# DS18B20_Control_Industry.net
KiCad netlist of a schematic drawn in Altium Designer
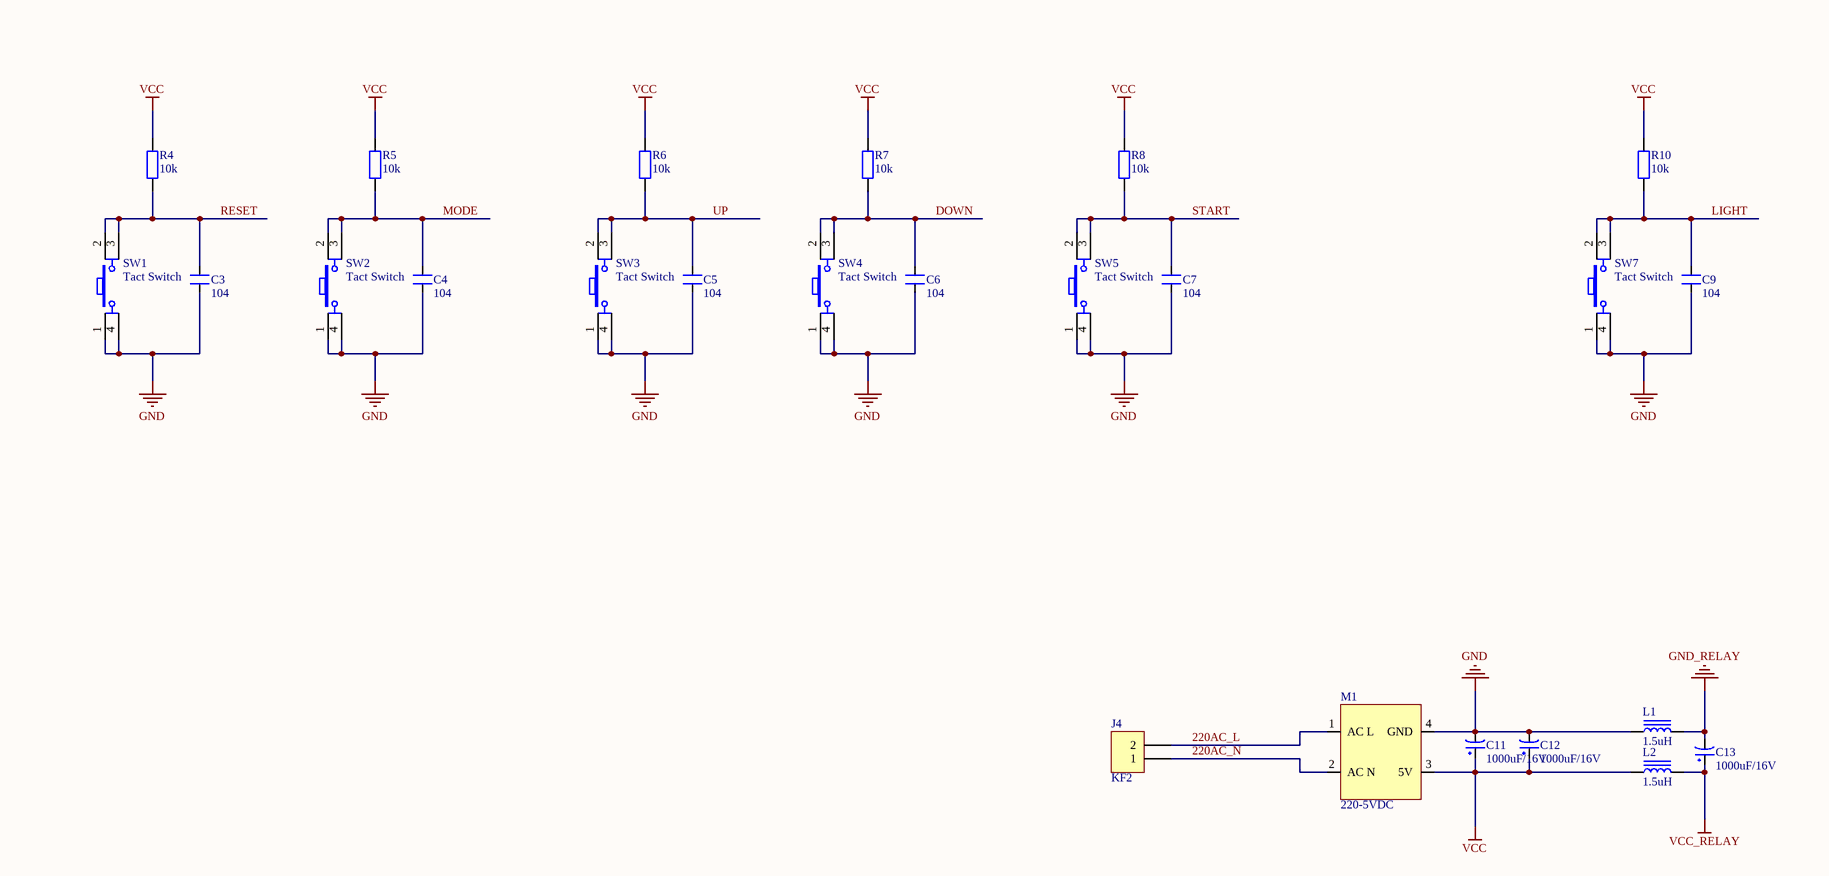
[diagram p0: DS18B20_Control_Industry.SchDoc, top left]
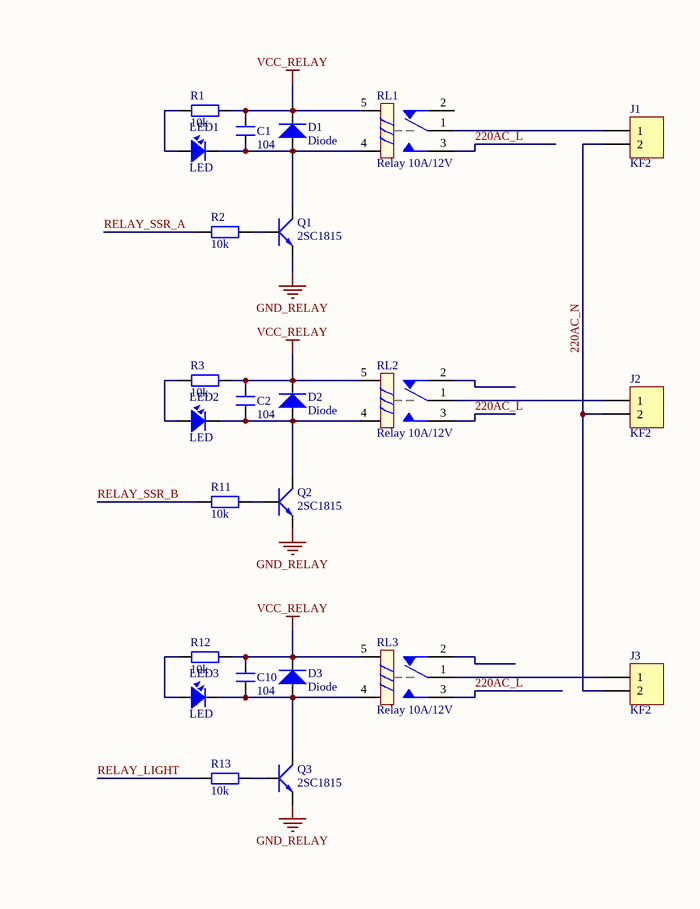
[diagram p1: DS18B20_Control_Industry.SchDoc, top right]
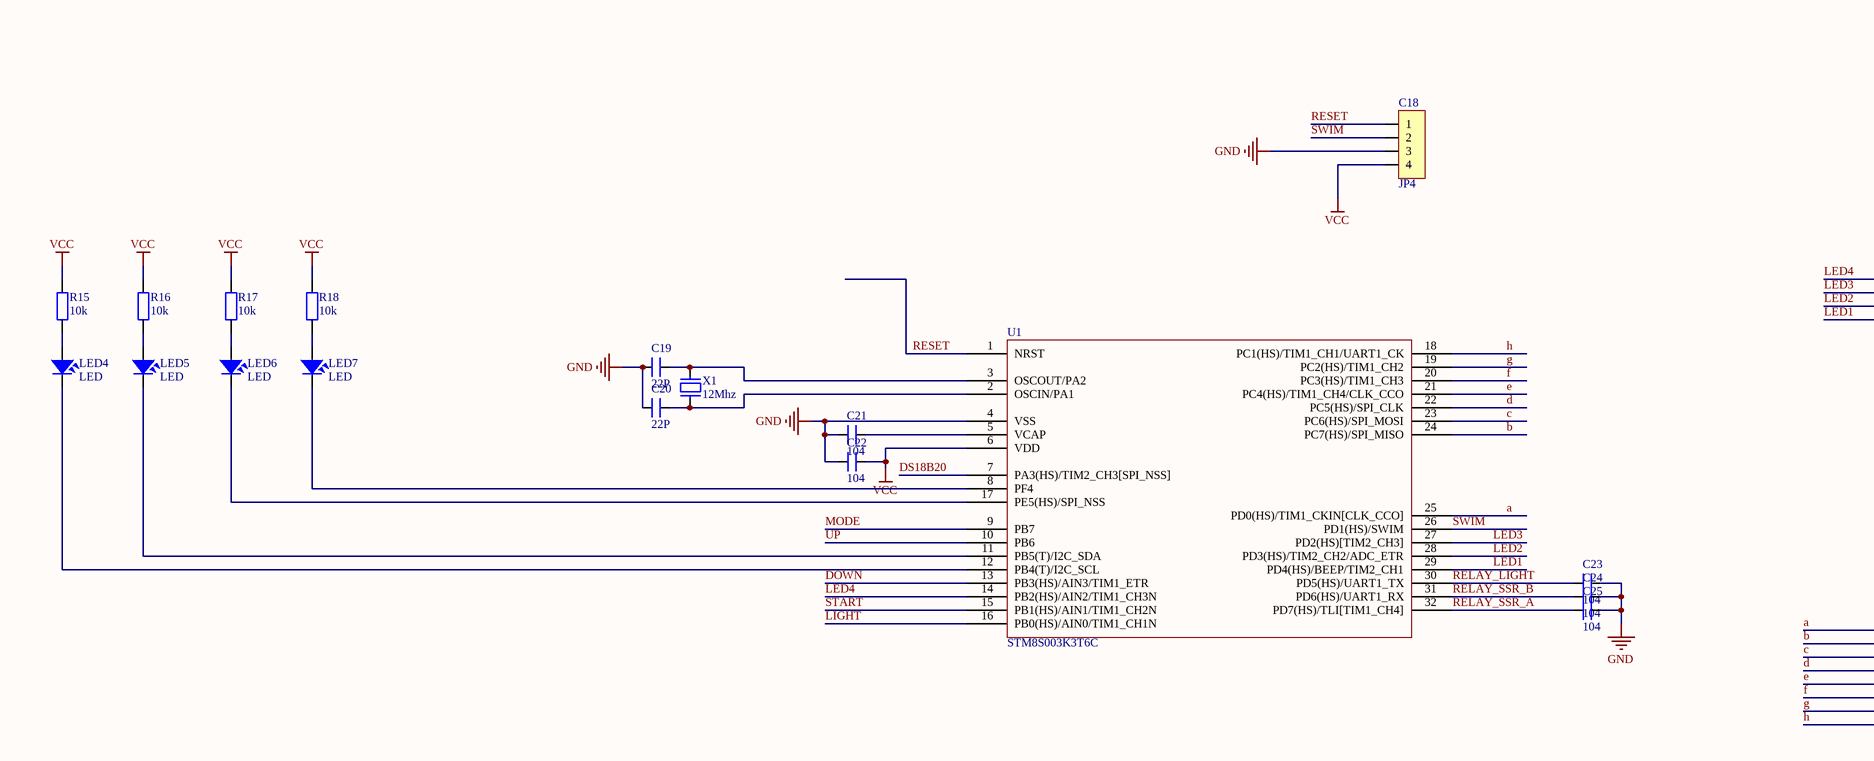
[diagram p2: DS18B20_Control_Industry.SchDoc, bottom left]
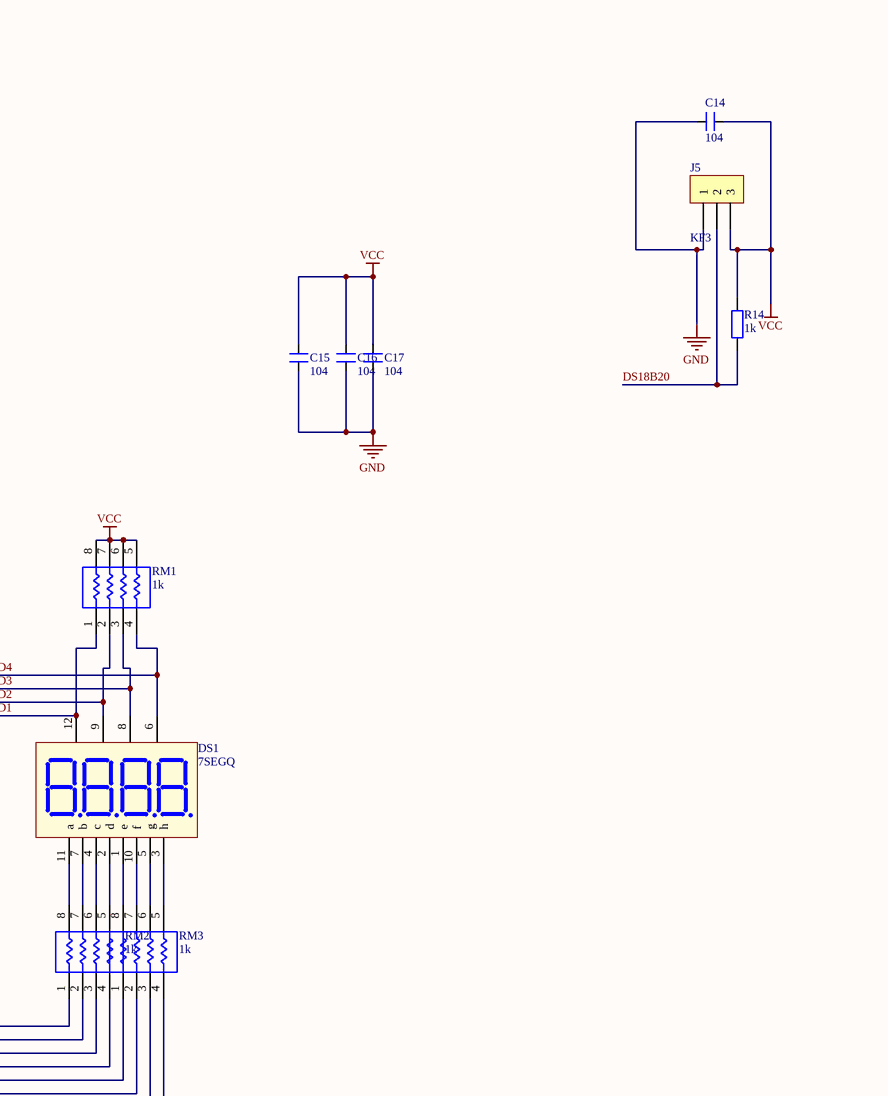
[diagram p3: DS18B20_Control_Industry.SchDoc, bottom right]

(export (version "E")
  (design (tool "Eeschema 10.0.6"))
  (components
    (comp (ref "C1")
      (value "104")
      (footprint "SM-0805")
      (description "Cap SMD")
      (libsource (lib "OBIT_TESLA") (part "CM"))
    )
    (comp (ref "C2")
      (value "104")
      (footprint "SM-0805")
      (description "Cap SMD")
      (libsource (lib "OBIT_TESLA") (part "CM"))
    )
    (comp (ref "C3")
      (value "104")
      (footprint "SM-0805")
      (description "Cap SMD")
      (libsource (lib "OBIT_TESLA") (part "CM"))
    )
    (comp (ref "C4")
      (value "104")
      (footprint "SM-0805")
      (description "Cap SMD")
      (libsource (lib "OBIT_TESLA") (part "CM"))
    )
    (comp (ref "C5")
      (value "104")
      (footprint "SM-0805")
      (description "Cap SMD")
      (libsource (lib "OBIT_TESLA") (part "CM"))
    )
    (comp (ref "C6")
      (value "104")
      (footprint "SM-0805")
      (description "Cap SMD")
      (libsource (lib "OBIT_TESLA") (part "CM"))
    )
    (comp (ref "C7")
      (value "104")
      (footprint "SM-0805")
      (description "Cap SMD")
      (libsource (lib "OBIT_TESLA") (part "CM"))
    )
    (comp (ref "C9")
      (value "104")
      (footprint "SM-0805")
      (description "Cap SMD")
      (libsource (lib "OBIT_TESLA") (part "CM"))
    )
    (comp (ref "C10")
      (value "104")
      (footprint "SM-0805")
      (description "Cap SMD")
      (libsource (lib "OBIT_TESLA") (part "CM"))
    )
    (comp (ref "C11")
      (value "1000uF/16V")
      (footprint "CP1.5/3.4")
      (description "Cap 1000uF/16V - 220uF/50V")
      (libsource (lib "OBIT_TESLA") (part "CP4"))
    )
    (comp (ref "C12")
      (value "1000uF/16V")
      (footprint "CP1.5/3.4")
      (description "Cap 1000uF/16V - 220uF/50V")
      (libsource (lib "OBIT_TESLA") (part "CP4"))
    )
    (comp (ref "C13")
      (value "1000uF/16V")
      (footprint "CP1.5/3.4")
      (description "Cap 1000uF/16V - 220uF/50V")
      (libsource (lib "OBIT_TESLA") (part "CP4"))
    )
    (comp (ref "C14")
      (value "104")
      (footprint "SM-0805")
      (description "Cap SMD")
      (libsource (lib "OBIT_TESLA") (part "CM"))
    )
    (comp (ref "C15")
      (value "104")
      (footprint "SM-0805")
      (description "Cap SMD")
      (libsource (lib "OBIT_TESLA") (part "CM"))
    )
    (comp (ref "C16")
      (value "104")
      (footprint "SM-0805")
      (description "Cap SMD")
      (libsource (lib "OBIT_TESLA") (part "CM"))
    )
    (comp (ref "C17")
      (value "104")
      (footprint "SM-0805")
      (description "Cap SMD")
      (libsource (lib "OBIT_TESLA") (part "CM"))
    )
    (comp (ref "C18")
      (value "JP4")
      (footprint "JP4-C1T")
      (description "WR-PHD 2.54 mm Angled Socket Header")
      (fields
        (field (name "MANUFACTURER") "Würth Elektronik eiSos GmbH")
        (field (name "PARTNO") "613004143121")
        (field (name "CREATED BY") "Karrer Zheng")
      )
      (libsource (lib "OBIT_TESLA") (part "JP4"))
    )
    (comp (ref "C19")
      (value "22P")
      (footprint "SM-0805")
      (description "Cap SMD")
      (libsource (lib "OBIT_TESLA") (part "CM"))
    )
    (comp (ref "C20")
      (value "22P")
      (footprint "SM-0805")
      (description "Cap SMD")
      (libsource (lib "OBIT_TESLA") (part "CM"))
    )
    (comp (ref "C21")
      (value "104")
      (footprint "SM-0805")
      (description "Cap SMD")
      (libsource (lib "OBIT_TESLA") (part "CM"))
    )
    (comp (ref "C22")
      (value "104")
      (footprint "SM-0805")
      (description "Cap SMD")
      (libsource (lib "OBIT_TESLA") (part "CM"))
    )
    (comp (ref "C23")
      (value "104")
      (footprint "SM-0805")
      (description "Cap SMD")
      (libsource (lib "OBIT_TESLA") (part "CM"))
    )
    (comp (ref "C24")
      (value "104")
      (footprint "SM-0805")
      (description "Cap SMD")
      (libsource (lib "OBIT_TESLA") (part "CM"))
    )
    (comp (ref "C25")
      (value "104")
      (footprint "SM-0805")
      (description "Cap SMD")
      (libsource (lib "OBIT_TESLA") (part "CM"))
    )
    (comp (ref "D1") (value "Diode") (footprint "DIO-SMD-106") (libsource (lib "OBIT_TESLA") (part "Diode")))
    (comp (ref "D2") (value "Diode") (footprint "DIO-SMD-106") (libsource (lib "OBIT_TESLA") (part "Diode")))
    (comp (ref "D3") (value "Diode") (footprint "DIO-SMD-106") (libsource (lib "OBIT_TESLA") (part "Diode")))
    (comp (ref "DS1")
      (value "7SEGQ")
      (footprint "7SEGQ")
      (description "Four 7 Seg Dipslay")
      (libsource (lib "Tesla_Thinh") (part "LED7Q"))
    )
    (comp (ref "J1")
      (value "KF2")
      (footprint "KF2-5.08")
      (fields
        (field (name "MANUFACTURER") "Würth Elektronik eiSos GmbH")
        (field (name "PARTNO") "691103110002")
        (field (name "CREATED BY") "Karrer Zheng")
      )
      (libsource (lib "OBIT_TESLA") (part "KF2"))
    )
    (comp (ref "J2")
      (value "KF2")
      (footprint "KF2-5.08")
      (fields
        (field (name "MANUFACTURER") "Würth Elektronik eiSos GmbH")
        (field (name "PARTNO") "691103110002")
        (field (name "CREATED BY") "Karrer Zheng")
      )
      (libsource (lib "OBIT_TESLA") (part "KF2"))
    )
    (comp (ref "J3")
      (value "KF2")
      (footprint "KF2-5.08")
      (fields
        (field (name "MANUFACTURER") "Würth Elektronik eiSos GmbH")
        (field (name "PARTNO") "691103110002")
        (field (name "CREATED BY") "Karrer Zheng")
      )
      (libsource (lib "OBIT_TESLA") (part "KF2"))
    )
    (comp (ref "J4")
      (value "KF2")
      (footprint "KF2-5.08")
      (fields
        (field (name "MANUFACTURER") "Würth Elektronik eiSos GmbH")
        (field (name "PARTNO") "691103110002")
        (field (name "CREATED BY") "Karrer Zheng")
      )
      (libsource (lib "") (part "KF2_1"))
    )
    (comp (ref "J5")
      (value "KF3")
      (footprint "KF3-5.08")
      (fields
        (field (name "MANUFACTURER") "Würth Elektronik eiSos GmbH")
        (field (name "PARTNO") "691103110003")
        (field (name "CREATED BY") "Karrer Zheng")
      )
      (libsource (lib "OBIT_TESLA") (part "KF3"))
    )
    (comp (ref "L1")
      (value "1.5uH")
      (footprint "BOURNS SRR6028")
      (description "SMT Inductor")
      (libsource (lib "OBIT_TESLA") (part "Inductor"))
    )
    (comp (ref "L2")
      (value "1.5uH")
      (footprint "BOURNS SRR6028")
      (description "SMT Inductor")
      (libsource (lib "OBIT_TESLA") (part "Inductor"))
    )
    (comp (ref "LED1")
      (value "LED")
      (footprint "SM-LED-0805-Blue")
      (libsource (lib "OBIT_TESLA") (part "LED"))
    )
    (comp (ref "LED2")
      (value "LED")
      (footprint "SM-LED-0805-Blue")
      (libsource (lib "OBIT_TESLA") (part "LED"))
    )
    (comp (ref "LED3")
      (value "LED")
      (footprint "SM-LED-0805-Blue")
      (libsource (lib "OBIT_TESLA") (part "LED"))
    )
    (comp (ref "LED4") (value "LED") (footprint "LED-5-BLUE") (libsource (lib "OBIT_TESLA") (part "LED")))
    (comp (ref "LED5") (value "LED") (footprint "LED-5-BLUE") (libsource (lib "OBIT_TESLA") (part "LED")))
    (comp (ref "LED6") (value "LED") (footprint "LED-5-BLUE") (libsource (lib "OBIT_TESLA") (part "LED")))
    (comp (ref "LED7") (value "LED") (footprint "LED-5-BLUE") (libsource (lib "OBIT_TESLA") (part "LED")))
    (comp (ref "M1")
      (value "220-5VDC")
      (footprint "5V 700mA 3.5W AC DC")
      (libsource (lib "OBIT_TESLA") (part "5V 700mA 3.5W AC 220 to DC"))
    )
    (comp (ref "Q1")
      (value "2SC1815")
      (footprint "SOT23-321")
      (description "NPN 600mW, ECB")
      (libsource (lib "OBIT_TESLA") (part "2SC1815"))
    )
    (comp (ref "Q2")
      (value "2SC1815")
      (footprint "SOT23-321")
      (description "NPN 600mW, ECB")
      (libsource (lib "OBIT_TESLA") (part "2SC1815"))
    )
    (comp (ref "Q3")
      (value "2SC1815")
      (footprint "SOT23-321")
      (description "NPN 600mW, ECB")
      (libsource (lib "OBIT_TESLA") (part "2SC1815"))
    )
    (comp (ref "R1")
      (value "10k")
      (footprint "RES-SMD-0805")
      (description "Resistor R1/4W")
      (libsource (lib "OBIT_TESLA") (part "R"))
    )
    (comp (ref "R2")
      (value "10k")
      (footprint "RES-SMD-0805")
      (description "Resistor R1/4W")
      (libsource (lib "OBIT_TESLA") (part "R"))
    )
    (comp (ref "R3")
      (value "10k")
      (footprint "RES-SMD-0805")
      (description "Resistor R1/4W")
      (libsource (lib "OBIT_TESLA") (part "R"))
    )
    (comp (ref "R4")
      (value "10k")
      (footprint "RES-SMD-0805")
      (description "Resistor R1/4W")
      (libsource (lib "OBIT_TESLA") (part "R"))
    )
    (comp (ref "R5")
      (value "10k")
      (footprint "RES-SMD-0805")
      (description "Resistor R1/4W")
      (libsource (lib "OBIT_TESLA") (part "R"))
    )
    (comp (ref "R6")
      (value "10k")
      (footprint "RES-SMD-0805")
      (description "Resistor R1/4W")
      (libsource (lib "OBIT_TESLA") (part "R"))
    )
    (comp (ref "R7")
      (value "10k")
      (footprint "RES-SMD-0805")
      (description "Resistor R1/4W")
      (libsource (lib "OBIT_TESLA") (part "R"))
    )
    (comp (ref "R8")
      (value "10k")
      (footprint "RES-SMD-0805")
      (description "Resistor R1/4W")
      (libsource (lib "OBIT_TESLA") (part "R"))
    )
    (comp (ref "R10")
      (value "10k")
      (footprint "RES-SMD-0805")
      (description "Resistor R1/4W")
      (libsource (lib "OBIT_TESLA") (part "R"))
    )
    (comp (ref "R11")
      (value "10k")
      (footprint "RES-SMD-0805")
      (description "Resistor R1/4W")
      (libsource (lib "OBIT_TESLA") (part "R"))
    )
    (comp (ref "R12")
      (value "10k")
      (footprint "RES-SMD-0805")
      (description "Resistor R1/4W")
      (libsource (lib "OBIT_TESLA") (part "R"))
    )
    (comp (ref "R13")
      (value "10k")
      (footprint "RES-SMD-0805")
      (description "Resistor R1/4W")
      (libsource (lib "OBIT_TESLA") (part "R"))
    )
    (comp (ref "R14")
      (value "1k")
      (footprint "RES-SMD-0805")
      (description "Resistor R1/4W")
      (libsource (lib "OBIT_TESLA") (part "R"))
    )
    (comp (ref "R15")
      (value "10k")
      (footprint "RES-SMD-0805")
      (description "Resistor R1/4W")
      (libsource (lib "OBIT_TESLA") (part "R"))
    )
    (comp (ref "R16")
      (value "10k")
      (footprint "RES-SMD-0805")
      (description "Resistor R1/4W")
      (libsource (lib "OBIT_TESLA") (part "R"))
    )
    (comp (ref "R17")
      (value "10k")
      (footprint "RES-SMD-0805")
      (description "Resistor R1/4W")
      (libsource (lib "OBIT_TESLA") (part "R"))
    )
    (comp (ref "R18")
      (value "10k")
      (footprint "RES-SMD-0805")
      (description "Resistor R1/4W")
      (libsource (lib "OBIT_TESLA") (part "R"))
    )
    (comp (ref "RL1")
      (value "Relay 10A/12V")
      (footprint "RL_SPDT_10A")
      (description "Relay SPDT,10A - 12VDC 5 Pin")
      (libsource (lib "OBIT_TESLA") (part "Relay 1"))
    )
    (comp (ref "RL2")
      (value "Relay 10A/12V")
      (footprint "RL_SPDT_10A")
      (description "Relay SPDT,10A - 12VDC 5 Pin")
      (libsource (lib "OBIT_TESLA") (part "Relay 1"))
    )
    (comp (ref "RL3")
      (value "Relay 10A/12V")
      (footprint "RL_SPDT_10A")
      (description "Relay SPDT,10A - 12VDC 5 Pin")
      (libsource (lib "OBIT_TESLA") (part "Relay 1"))
    )
    (comp (ref "RM1") (value "1k") (footprint "RN4-0805") (libsource (lib "OBIT_TESLA") (part "ResPack")))
    (comp (ref "RM2") (value "1k") (footprint "RN4-0805") (libsource (lib "OBIT_TESLA") (part "ResPack")))
    (comp (ref "RM3") (value "1k") (footprint "RN4-0805") (libsource (lib "OBIT_TESLA") (part "ResPack")))
    (comp (ref "SW1")
      (value "Tact Switch")
      (footprint "SW4_12x12")
      (libsource (lib "OBIT_TESLA") (part "SW4"))
    )
    (comp (ref "SW2")
      (value "Tact Switch")
      (footprint "SW4_12x12")
      (libsource (lib "OBIT_TESLA") (part "SW4"))
    )
    (comp (ref "SW3")
      (value "Tact Switch")
      (footprint "SW4_12x12")
      (libsource (lib "OBIT_TESLA") (part "SW4"))
    )
    (comp (ref "SW4")
      (value "Tact Switch")
      (footprint "SW4_12x12")
      (libsource (lib "OBIT_TESLA") (part "SW4"))
    )
    (comp (ref "SW5")
      (value "Tact Switch")
      (footprint "SW4_12x12")
      (libsource (lib "OBIT_TESLA") (part "SW4"))
    )
    (comp (ref "SW7")
      (value "Tact Switch")
      (footprint "SW4_12x12")
      (libsource (lib "OBIT_TESLA") (part "SW4"))
    )
    (comp (ref "U1")
      (value "STM8S003K3T6C")
      (footprint "LQFP32T30")
      (libsource (lib "OBIT_TESLA") (part "STM8S003K3T6C"))
    )
    (comp (ref "X1")
      (value "12Mhz")
      (footprint "XT2")
      (description "Crystal, 32.768 KHz, -40 to 85 degC, 3.2 x 1.5 x 0.9 mm SMD")
      (libsource (lib "OBIT_TESLA") (part "XT2"))
    )
  )
  (nets
    (net (code "1") (name "/220AC_L") (class "Default")
      (node (ref "J4") (pin "2") (pinfunction "2_2") (pintype "passive"))
      (node (ref "M1") (pin "1") (pinfunction "AC_L_1") (pintype "passive"))
      (node (ref "RL1") (pin "3") (pinfunction "3_3") (pintype "passive"))
      (node (ref "RL2") (pin "3") (pinfunction "3_3") (pintype "passive"))
      (node (ref "RL3") (pin "3") (pinfunction "3_3") (pintype "passive"))
    )
    (net (code "2") (name "/220AC_N") (class "Default")
      (node (ref "J1") (pin "2") (pinfunction "2_2") (pintype "passive"))
      (node (ref "J2") (pin "2") (pinfunction "2_2") (pintype "passive"))
      (node (ref "J3") (pin "2") (pinfunction "2_2") (pintype "passive"))
      (node (ref "J4") (pin "1") (pinfunction "1_1") (pintype "passive"))
      (node (ref "M1") (pin "2") (pinfunction "AC_N_2") (pintype "passive"))
    )
    (net (code "3") (name "/DOWN") (class "Default")
      (node (ref "C6") (pin "2") (pinfunction "2_2") (pintype "passive"))
      (node (ref "R7") (pin "2") (pinfunction "2_2") (pintype "passive"))
      (node (ref "SW4") (pin "2") (pintype "passive"))
      (node (ref "SW4") (pin "3") (pintype "passive"))
      (node (ref "U1") (pin "13") (pinfunction "PB3(HS)/AIN3/TIM1_ETR_13") (pintype "passive"))
    )
    (net (code "4") (name "/DS18B20") (class "Default")
      (node (ref "J5") (pin "2") (pinfunction "2_2") (pintype "passive"))
      (node (ref "R14") (pin "1") (pinfunction "1_1") (pintype "passive"))
      (node (ref "U1") (pin "7") (pinfunction "PA3(HS)/TIM2_CH3[SPI_NSS]_7") (pintype "passive"))
    )
    (net (code "5") (name "/LED1") (class "Default")
      (node (ref "DS1") (pin "12") (pinfunction "V1_12") (pintype "passive"))
      (node (ref "RM1") (pin "1") (pinfunction "1_1") (pintype "passive"))
      (node (ref "U1") (pin "29") (pinfunction "PD4(HS)/BEEP/TIM2_CH1_29") (pintype "passive"))
    )
    (net (code "6") (name "/LED2") (class "Default")
      (node (ref "DS1") (pin "9") (pinfunction "V2_9") (pintype "passive"))
      (node (ref "RM1") (pin "2") (pinfunction "2_2") (pintype "passive"))
      (node (ref "U1") (pin "28") (pinfunction "PD3(HS)/TIM2_CH2/ADC_ETR_28") (pintype "passive"))
    )
    (net (code "7") (name "/LED3") (class "Default")
      (node (ref "DS1") (pin "8") (pinfunction "V3_8") (pintype "passive"))
      (node (ref "RM1") (pin "3") (pinfunction "3_3") (pintype "passive"))
      (node (ref "U1") (pin "27") (pinfunction "PD2(HS)[TIM2_CH3]_27") (pintype "passive"))
    )
    (net (code "8") (name "/LED4") (class "Default")
      (node (ref "DS1") (pin "6") (pinfunction "V4_6") (pintype "passive"))
      (node (ref "RM1") (pin "4") (pinfunction "4_4") (pintype "passive"))
      (node (ref "U1") (pin "14") (pinfunction "PB2(HS)/AIN2/TIM1_CH3N_14") (pintype "passive"))
    )
    (net (code "9") (name "/LIGHT") (class "Default")
      (node (ref "C9") (pin "2") (pinfunction "2_2") (pintype "passive"))
      (node (ref "R10") (pin "2") (pinfunction "2_2") (pintype "passive"))
      (node (ref "SW7") (pin "2") (pintype "passive"))
      (node (ref "SW7") (pin "3") (pintype "passive"))
      (node (ref "U1") (pin "16") (pinfunction "PB0(HS)/AIN0/TIM1_CH1N_16") (pintype "passive"))
    )
    (net (code "10") (name "/MODE") (class "Default")
      (node (ref "C4") (pin "2") (pinfunction "2_2") (pintype "passive"))
      (node (ref "R5") (pin "2") (pinfunction "2_2") (pintype "passive"))
      (node (ref "SW2") (pin "2") (pintype "passive"))
      (node (ref "SW2") (pin "3") (pintype "passive"))
      (node (ref "U1") (pin "9") (pinfunction "PB7_9") (pintype "passive"))
    )
    (net (code "11") (name "/RELAY_LIGHT") (class "Default")
      (node (ref "C23") (pin "2") (pinfunction "2_2") (pintype "passive"))
      (node (ref "R13") (pin "2") (pinfunction "2_2") (pintype "passive"))
      (node (ref "U1") (pin "30") (pinfunction "PD5(HS)/UART1_TX_30") (pintype "passive"))
    )
    (net (code "12") (name "/RELAY_SSR_A") (class "Default")
      (node (ref "C25") (pin "2") (pinfunction "2_2") (pintype "passive"))
      (node (ref "R2") (pin "2") (pinfunction "2_2") (pintype "passive"))
      (node (ref "U1") (pin "32") (pinfunction "PD7(HS)/TLI[TIM1_CH4]_32") (pintype "passive"))
    )
    (net (code "13") (name "/RELAY_SSR_B") (class "Default")
      (node (ref "C24") (pin "2") (pinfunction "2_2") (pintype "passive"))
      (node (ref "R11") (pin "2") (pinfunction "2_2") (pintype "passive"))
      (node (ref "U1") (pin "31") (pinfunction "PD6(HS)/UART1_RX_31") (pintype "passive"))
    )
    (net (code "14") (name "/RESET") (class "Default")
      (node (ref "C18") (pin "1") (pinfunction "1_1") (pintype "passive"))
      (node (ref "C3") (pin "2") (pinfunction "2_2") (pintype "passive"))
      (node (ref "R4") (pin "2") (pinfunction "2_2") (pintype "passive"))
      (node (ref "SW1") (pin "2") (pintype "passive"))
      (node (ref "SW1") (pin "3") (pintype "passive"))
      (node (ref "U1") (pin "1") (pinfunction "NRST_1") (pintype "passive"))
    )
    (net (code "15") (name "/START") (class "Default")
      (node (ref "C7") (pin "2") (pinfunction "2_2") (pintype "passive"))
      (node (ref "R8") (pin "2") (pinfunction "2_2") (pintype "passive"))
      (node (ref "SW5") (pin "2") (pintype "passive"))
      (node (ref "SW5") (pin "3") (pintype "passive"))
      (node (ref "U1") (pin "15") (pinfunction "PB1(HS)/AIN1/TIM1_CH2N_15") (pintype "passive"))
    )
    (net (code "16") (name "/SWIM") (class "Default")
      (node (ref "C18") (pin "2") (pinfunction "2_2") (pintype "passive"))
      (node (ref "U1") (pin "26") (pinfunction "PD1(HS)/SWIM_26") (pintype "passive"))
    )
    (net (code "17") (name "/UP") (class "Default")
      (node (ref "C5") (pin "2") (pinfunction "2_2") (pintype "passive"))
      (node (ref "R6") (pin "2") (pinfunction "2_2") (pintype "passive"))
      (node (ref "SW3") (pin "2") (pintype "passive"))
      (node (ref "SW3") (pin "3") (pintype "passive"))
      (node (ref "U1") (pin "10") (pinfunction "PB6_10") (pintype "passive"))
    )
    (net (code "18") (name "/a") (class "Default")
      (node (ref "RM2") (pin "1") (pinfunction "1_1") (pintype "passive"))
      (node (ref "U1") (pin "25") (pinfunction "PD0(HS)/TIM1_CKIN[CLK_CCO]_25") (pintype "passive"))
    )
    (net (code "19") (name "/b") (class "Default")
      (node (ref "RM2") (pin "2") (pinfunction "2_2") (pintype "passive"))
      (node (ref "U1") (pin "24") (pinfunction "PC7(HS)/SPI_MISO_24") (pintype "passive"))
    )
    (net (code "20") (name "/c") (class "Default")
      (node (ref "RM2") (pin "3") (pinfunction "3_3") (pintype "passive"))
      (node (ref "U1") (pin "23") (pinfunction "PC6(HS)/SPI_MOSI_23") (pintype "passive"))
    )
    (net (code "21") (name "/d") (class "Default")
      (node (ref "RM2") (pin "4") (pinfunction "4_4") (pintype "passive"))
      (node (ref "U1") (pin "22") (pinfunction "PC5(HS)/SPI_CLK_22") (pintype "passive"))
    )
    (net (code "22") (name "/e") (class "Default")
      (node (ref "RM3") (pin "1") (pinfunction "1_1") (pintype "passive"))
      (node (ref "U1") (pin "21") (pinfunction "PC4(HS)/TIM1_CH4/CLK_CCO_21") (pintype "passive"))
    )
    (net (code "23") (name "/f") (class "Default")
      (node (ref "RM3") (pin "2") (pinfunction "2_2") (pintype "passive"))
      (node (ref "U1") (pin "20") (pinfunction "PC3(HS)/TIM1_CH3_20") (pintype "passive"))
    )
    (net (code "24") (name "/g") (class "Default")
      (node (ref "RM3") (pin "3") (pinfunction "3_3") (pintype "passive"))
      (node (ref "U1") (pin "19") (pinfunction "PC2(HS)/TIM1_CH2_19") (pintype "passive"))
    )
    (net (code "25") (name "/h") (class "Default")
      (node (ref "RM3") (pin "4") (pinfunction "4_4") (pintype "passive"))
      (node (ref "U1") (pin "18") (pinfunction "PC1(HS)/TIM1_CH1/UART1_CK_18") (pintype "passive"))
    )
    (net (code "26") (name "GND") (class "Default")
      (node (ref "C11") (pin "2") (pinfunction "2_2") (pintype "passive"))
      (node (ref "C12") (pin "2") (pinfunction "2_2") (pintype "passive"))
      (node (ref "C14") (pin "1") (pinfunction "1_1") (pintype "passive"))
      (node (ref "C15") (pin "1") (pinfunction "1_1") (pintype "passive"))
      (node (ref "C16") (pin "1") (pinfunction "1_1") (pintype "passive"))
      (node (ref "C17") (pin "1") (pinfunction "1_1") (pintype "passive"))
      (node (ref "C18") (pin "3") (pinfunction "3_3") (pintype "passive"))
      (node (ref "C19") (pin "1") (pinfunction "1_1") (pintype "passive"))
      (node (ref "C20") (pin "1") (pinfunction "1_1") (pintype "passive"))
      (node (ref "C21") (pin "1") (pinfunction "1_1") (pintype "passive"))
      (node (ref "C22") (pin "1") (pinfunction "1_1") (pintype "passive"))
      (node (ref "C23") (pin "1") (pinfunction "1_1") (pintype "passive"))
      (node (ref "C24") (pin "1") (pinfunction "1_1") (pintype "passive"))
      (node (ref "C25") (pin "1") (pinfunction "1_1") (pintype "passive"))
      (node (ref "C3") (pin "1") (pinfunction "1_1") (pintype "passive"))
      (node (ref "C4") (pin "1") (pinfunction "1_1") (pintype "passive"))
      (node (ref "C5") (pin "1") (pinfunction "1_1") (pintype "passive"))
      (node (ref "C6") (pin "1") (pinfunction "1_1") (pintype "passive"))
      (node (ref "C7") (pin "1") (pinfunction "1_1") (pintype "passive"))
      (node (ref "C9") (pin "1") (pinfunction "1_1") (pintype "passive"))
      (node (ref "J5") (pin "1") (pinfunction "1_1") (pintype "passive"))
      (node (ref "L1") (pin "1") (pinfunction "1_1") (pintype "passive"))
      (node (ref "M1") (pin "4") (pinfunction "GND_4") (pintype "passive"))
      (node (ref "SW1") (pin "1") (pintype "passive"))
      (node (ref "SW1") (pin "4") (pintype "passive"))
      (node (ref "SW2") (pin "1") (pintype "passive"))
      (node (ref "SW2") (pin "4") (pintype "passive"))
      (node (ref "SW3") (pin "1") (pintype "passive"))
      (node (ref "SW3") (pin "4") (pintype "passive"))
      (node (ref "SW4") (pin "1") (pintype "passive"))
      (node (ref "SW4") (pin "4") (pintype "passive"))
      (node (ref "SW5") (pin "1") (pintype "passive"))
      (node (ref "SW5") (pin "4") (pintype "passive"))
      (node (ref "SW7") (pin "1") (pintype "passive"))
      (node (ref "SW7") (pin "4") (pintype "passive"))
      (node (ref "U1") (pin "4") (pinfunction "VSS_4") (pintype "passive"))
    )
    (net (code "27") (name "GND_RELAY") (class "Default")
      (node (ref "C13") (pin "2") (pinfunction "2_2") (pintype "passive"))
      (node (ref "L1") (pin "2") (pinfunction "2_2") (pintype "passive"))
      (node (ref "Q1") (pin "1") (pinfunction "E_1") (pintype "passive"))
      (node (ref "Q2") (pin "1") (pinfunction "E_1") (pintype "passive"))
      (node (ref "Q3") (pin "1") (pinfunction "E_1") (pintype "passive"))
    )
    (net (code "28") (name "Net-(DS1-a)") (class "Default")
      (node (ref "DS1") (pin "11") (pinfunction "a_11") (pintype "passive"))
      (node (ref "RM2") (pin "8") (pinfunction "8_8") (pintype "passive"))
    )
    (net (code "29") (name "Net-(DS1-b)") (class "Default")
      (node (ref "DS1") (pin "7") (pinfunction "b_7") (pintype "passive"))
      (node (ref "RM2") (pin "7") (pinfunction "7_7") (pintype "passive"))
    )
    (net (code "30") (name "Net-(DS1-c)") (class "Default")
      (node (ref "DS1") (pin "4") (pinfunction "c_4") (pintype "passive"))
      (node (ref "RM2") (pin "6") (pinfunction "6_6") (pintype "passive"))
    )
    (net (code "31") (name "Net-(DS1-d)") (class "Default")
      (node (ref "DS1") (pin "2") (pinfunction "d_2") (pintype "passive"))
      (node (ref "RM2") (pin "5") (pinfunction "5_5") (pintype "passive"))
    )
    (net (code "32") (name "Net-(DS1-e)") (class "Default")
      (node (ref "DS1") (pin "1") (pinfunction "e_1") (pintype "passive"))
      (node (ref "RM3") (pin "8") (pinfunction "8_8") (pintype "passive"))
    )
    (net (code "33") (name "Net-(DS1-f)") (class "Default")
      (node (ref "DS1") (pin "10") (pinfunction "f_10") (pintype "passive"))
      (node (ref "RM3") (pin "7") (pinfunction "7_7") (pintype "passive"))
    )
    (net (code "34") (name "Net-(DS1-g)") (class "Default")
      (node (ref "DS1") (pin "5") (pinfunction "g_5") (pintype "passive"))
      (node (ref "RM3") (pin "6") (pinfunction "6_6") (pintype "passive"))
    )
    (net (code "35") (name "Net-(DS1-h)") (class "Default")
      (node (ref "DS1") (pin "3") (pinfunction "h_3") (pintype "passive"))
      (node (ref "RM3") (pin "5") (pinfunction "5_5") (pintype "passive"))
    )
    (net (code "36") (name "Net-(J1-Pad1)") (class "Default")
      (node (ref "J1") (pin "1") (pinfunction "1_1") (pintype "passive"))
      (node (ref "RL1") (pin "1") (pinfunction "1_1") (pintype "passive"))
    )
    (net (code "37") (name "Net-(J2-Pad1)") (class "Default")
      (node (ref "J2") (pin "1") (pinfunction "1_1") (pintype "passive"))
      (node (ref "RL2") (pin "1") (pinfunction "1_1") (pintype "passive"))
    )
    (net (code "38") (name "Net-(J3-Pad1)") (class "Default")
      (node (ref "J3") (pin "1") (pinfunction "1_1") (pintype "passive"))
      (node (ref "RL3") (pin "1") (pinfunction "1_1") (pintype "passive"))
    )
    (net (code "39") (name "Net-(LED1-Pad1)") (class "Default")
      (node (ref "LED1") (pin "1") (pinfunction "1_1") (pintype "passive"))
      (node (ref "R1") (pin "2") (pinfunction "2_2") (pintype "passive"))
    )
    (net (code "40") (name "Net-(LED2-Pad1)") (class "Default")
      (node (ref "LED2") (pin "1") (pinfunction "1_1") (pintype "passive"))
      (node (ref "R3") (pin "2") (pinfunction "2_2") (pintype "passive"))
    )
    (net (code "41") (name "Net-(LED3-Pad1)") (class "Default")
      (node (ref "LED3") (pin "1") (pinfunction "1_1") (pintype "passive"))
      (node (ref "R12") (pin "2") (pinfunction "2_2") (pintype "passive"))
    )
    (net (code "42") (name "Net-(LED4-Pad1)") (class "Default")
      (node (ref "LED4") (pin "1") (pinfunction "1_1") (pintype "passive"))
      (node (ref "R15") (pin "1") (pinfunction "1_1") (pintype "passive"))
    )
    (net (code "43") (name "Net-(LED5-Pad1)") (class "Default")
      (node (ref "LED5") (pin "1") (pinfunction "1_1") (pintype "passive"))
      (node (ref "R16") (pin "1") (pinfunction "1_1") (pintype "passive"))
    )
    (net (code "44") (name "Net-(LED6-Pad1)") (class "Default")
      (node (ref "LED6") (pin "1") (pinfunction "1_1") (pintype "passive"))
      (node (ref "R17") (pin "1") (pinfunction "1_1") (pintype "passive"))
    )
    (net (code "45") (name "Net-(LED7-Pad1)") (class "Default")
      (node (ref "LED7") (pin "1") (pinfunction "1_1") (pintype "passive"))
      (node (ref "R18") (pin "1") (pinfunction "1_1") (pintype "passive"))
    )
    (net (code "46") (name "Net-(Q1-B)") (class "Default")
      (node (ref "Q1") (pin "3") (pinfunction "B_3") (pintype "passive"))
      (node (ref "R2") (pin "1") (pinfunction "1_1") (pintype "passive"))
    )
    (net (code "47") (name "Net-(Q1-C)") (class "Default")
      (node (ref "C1") (pin "1") (pinfunction "1_1") (pintype "passive"))
      (node (ref "D1") (pin "1") (pinfunction "1_1") (pintype "passive"))
      (node (ref "LED1") (pin "2") (pinfunction "2_2") (pintype "passive"))
      (node (ref "Q1") (pin "2") (pinfunction "C_2") (pintype "passive"))
      (node (ref "RL1") (pin "4") (pinfunction "4_4") (pintype "passive"))
    )
    (net (code "48") (name "Net-(Q2-B)") (class "Default")
      (node (ref "Q2") (pin "3") (pinfunction "B_3") (pintype "passive"))
      (node (ref "R11") (pin "1") (pinfunction "1_1") (pintype "passive"))
    )
    (net (code "49") (name "Net-(Q2-C)") (class "Default")
      (node (ref "C2") (pin "1") (pinfunction "1_1") (pintype "passive"))
      (node (ref "D2") (pin "1") (pinfunction "1_1") (pintype "passive"))
      (node (ref "LED2") (pin "2") (pinfunction "2_2") (pintype "passive"))
      (node (ref "Q2") (pin "2") (pinfunction "C_2") (pintype "passive"))
      (node (ref "RL2") (pin "4") (pinfunction "4_4") (pintype "passive"))
    )
    (net (code "50") (name "Net-(Q3-B)") (class "Default")
      (node (ref "Q3") (pin "3") (pinfunction "B_3") (pintype "passive"))
      (node (ref "R13") (pin "1") (pinfunction "1_1") (pintype "passive"))
    )
    (net (code "51") (name "Net-(Q3-C)") (class "Default")
      (node (ref "C10") (pin "1") (pinfunction "1_1") (pintype "passive"))
      (node (ref "D3") (pin "1") (pinfunction "1_1") (pintype "passive"))
      (node (ref "LED3") (pin "2") (pinfunction "2_2") (pintype "passive"))
      (node (ref "Q3") (pin "2") (pinfunction "C_2") (pintype "passive"))
      (node (ref "RL3") (pin "4") (pinfunction "4_4") (pintype "passive"))
    )
    (net (code "52") (name "Net-(U1-OSCIN{slash}PA1)") (class "Default")
      (node (ref "C20") (pin "2") (pinfunction "2_2") (pintype "passive"))
      (node (ref "U1") (pin "2") (pinfunction "OSCIN/PA1_2") (pintype "passive"))
      (node (ref "X1") (pin "1") (pinfunction "1_1") (pintype "passive"))
    )
    (net (code "53") (name "Net-(U1-OSCOUT{slash}PA2)") (class "Default")
      (node (ref "C19") (pin "2") (pinfunction "2_2") (pintype "passive"))
      (node (ref "U1") (pin "3") (pinfunction "OSCOUT/PA2_3") (pintype "passive"))
      (node (ref "X1") (pin "2") (pinfunction "2_2") (pintype "passive"))
    )
    (net (code "54") (name "Net-(U1-PB4(T){slash}I2C_SCL)") (class "Default")
      (node (ref "LED4") (pin "2") (pinfunction "2_2") (pintype "passive"))
      (node (ref "U1") (pin "12") (pinfunction "PB4(T)/I2C_SCL_12") (pintype "passive"))
    )
    (net (code "55") (name "Net-(U1-PB5(T){slash}I2C_SDA)") (class "Default")
      (node (ref "LED5") (pin "2") (pinfunction "2_2") (pintype "passive"))
      (node (ref "U1") (pin "11") (pinfunction "PB5(T)/I2C_SDA_11") (pintype "passive"))
    )
    (net (code "56") (name "Net-(U1-PE5(HS){slash}SPI_NSS)") (class "Default")
      (node (ref "LED6") (pin "2") (pinfunction "2_2") (pintype "passive"))
      (node (ref "U1") (pin "17") (pinfunction "PE5(HS)/SPI_NSS_17") (pintype "passive"))
    )
    (net (code "57") (name "Net-(U1-PF4)") (class "Default")
      (node (ref "LED7") (pin "2") (pinfunction "2_2") (pintype "passive"))
      (node (ref "U1") (pin "8") (pinfunction "PF4_8") (pintype "passive"))
    )
    (net (code "58") (name "Net-(U1-VCAP)") (class "Default")
      (node (ref "C21") (pin "2") (pinfunction "2_2") (pintype "passive"))
      (node (ref "U1") (pin "5") (pinfunction "VCAP_5") (pintype "passive"))
    )
    (net (code "59") (name "VCC") (class "Default")
      (node (ref "C11") (pin "1") (pinfunction "1_1") (pintype "passive"))
      (node (ref "C12") (pin "1") (pinfunction "1_1") (pintype "passive"))
      (node (ref "C14") (pin "2") (pinfunction "2_2") (pintype "passive"))
      (node (ref "C15") (pin "2") (pinfunction "2_2") (pintype "passive"))
      (node (ref "C16") (pin "2") (pinfunction "2_2") (pintype "passive"))
      (node (ref "C17") (pin "2") (pinfunction "2_2") (pintype "passive"))
      (node (ref "C18") (pin "4") (pinfunction "4_4") (pintype "passive"))
      (node (ref "C22") (pin "2") (pinfunction "2_2") (pintype "passive"))
      (node (ref "J5") (pin "3") (pinfunction "3_3") (pintype "passive"))
      (node (ref "L2") (pin "1") (pinfunction "1_1") (pintype "passive"))
      (node (ref "M1") (pin "3") (pinfunction "5V_3") (pintype "passive"))
      (node (ref "R10") (pin "1") (pinfunction "1_1") (pintype "passive"))
      (node (ref "R14") (pin "2") (pinfunction "2_2") (pintype "passive"))
      (node (ref "R15") (pin "2") (pinfunction "2_2") (pintype "passive"))
      (node (ref "R16") (pin "2") (pinfunction "2_2") (pintype "passive"))
      (node (ref "R17") (pin "2") (pinfunction "2_2") (pintype "passive"))
      (node (ref "R18") (pin "2") (pinfunction "2_2") (pintype "passive"))
      (node (ref "R4") (pin "1") (pinfunction "1_1") (pintype "passive"))
      (node (ref "R5") (pin "1") (pinfunction "1_1") (pintype "passive"))
      (node (ref "R6") (pin "1") (pinfunction "1_1") (pintype "passive"))
      (node (ref "R7") (pin "1") (pinfunction "1_1") (pintype "passive"))
      (node (ref "R8") (pin "1") (pinfunction "1_1") (pintype "passive"))
      (node (ref "RM1") (pin "5") (pinfunction "5_5") (pintype "passive"))
      (node (ref "RM1") (pin "6") (pinfunction "6_6") (pintype "passive"))
      (node (ref "RM1") (pin "7") (pinfunction "7_7") (pintype "passive"))
      (node (ref "RM1") (pin "8") (pinfunction "8_8") (pintype "passive"))
      (node (ref "U1") (pin "6") (pinfunction "VDD_6") (pintype "passive"))
    )
    (net (code "60") (name "VCC_RELAY") (class "Default")
      (node (ref "C1") (pin "2") (pinfunction "2_2") (pintype "passive"))
      (node (ref "C10") (pin "2") (pinfunction "2_2") (pintype "passive"))
      (node (ref "C13") (pin "1") (pinfunction "1_1") (pintype "passive"))
      (node (ref "C2") (pin "2") (pinfunction "2_2") (pintype "passive"))
      (node (ref "D1") (pin "2") (pinfunction "2_2") (pintype "passive"))
      (node (ref "D2") (pin "2") (pinfunction "2_2") (pintype "passive"))
      (node (ref "D3") (pin "2") (pinfunction "2_2") (pintype "passive"))
      (node (ref "L2") (pin "2") (pinfunction "2_2") (pintype "passive"))
      (node (ref "R1") (pin "1") (pinfunction "1_1") (pintype "passive"))
      (node (ref "R12") (pin "1") (pinfunction "1_1") (pintype "passive"))
      (node (ref "R3") (pin "1") (pinfunction "1_1") (pintype "passive"))
      (node (ref "RL1") (pin "5") (pinfunction "5_5") (pintype "passive"))
      (node (ref "RL2") (pin "5") (pinfunction "5_5") (pintype "passive"))
      (node (ref "RL3") (pin "5") (pinfunction "5_5") (pintype "passive"))
    )
    (net (code "61") (name "unconnected-(RL1-Pad2)") (class "Default")
      (node (ref "RL1") (pin "2") (pinfunction "2_2") (pintype "passive"))
    )
    (net (code "62") (name "unconnected-(RL2-Pad2)") (class "Default")
      (node (ref "RL2") (pin "2") (pinfunction "2_2") (pintype "passive"))
    )
    (net (code "63") (name "unconnected-(RL3-Pad2)") (class "Default")
      (node (ref "RL3") (pin "2") (pinfunction "2_2") (pintype "passive"))
    )
  )
)
